# 07_LMS7002M_Power.net
KiCad netlist of a schematic drawn in Altium Designer
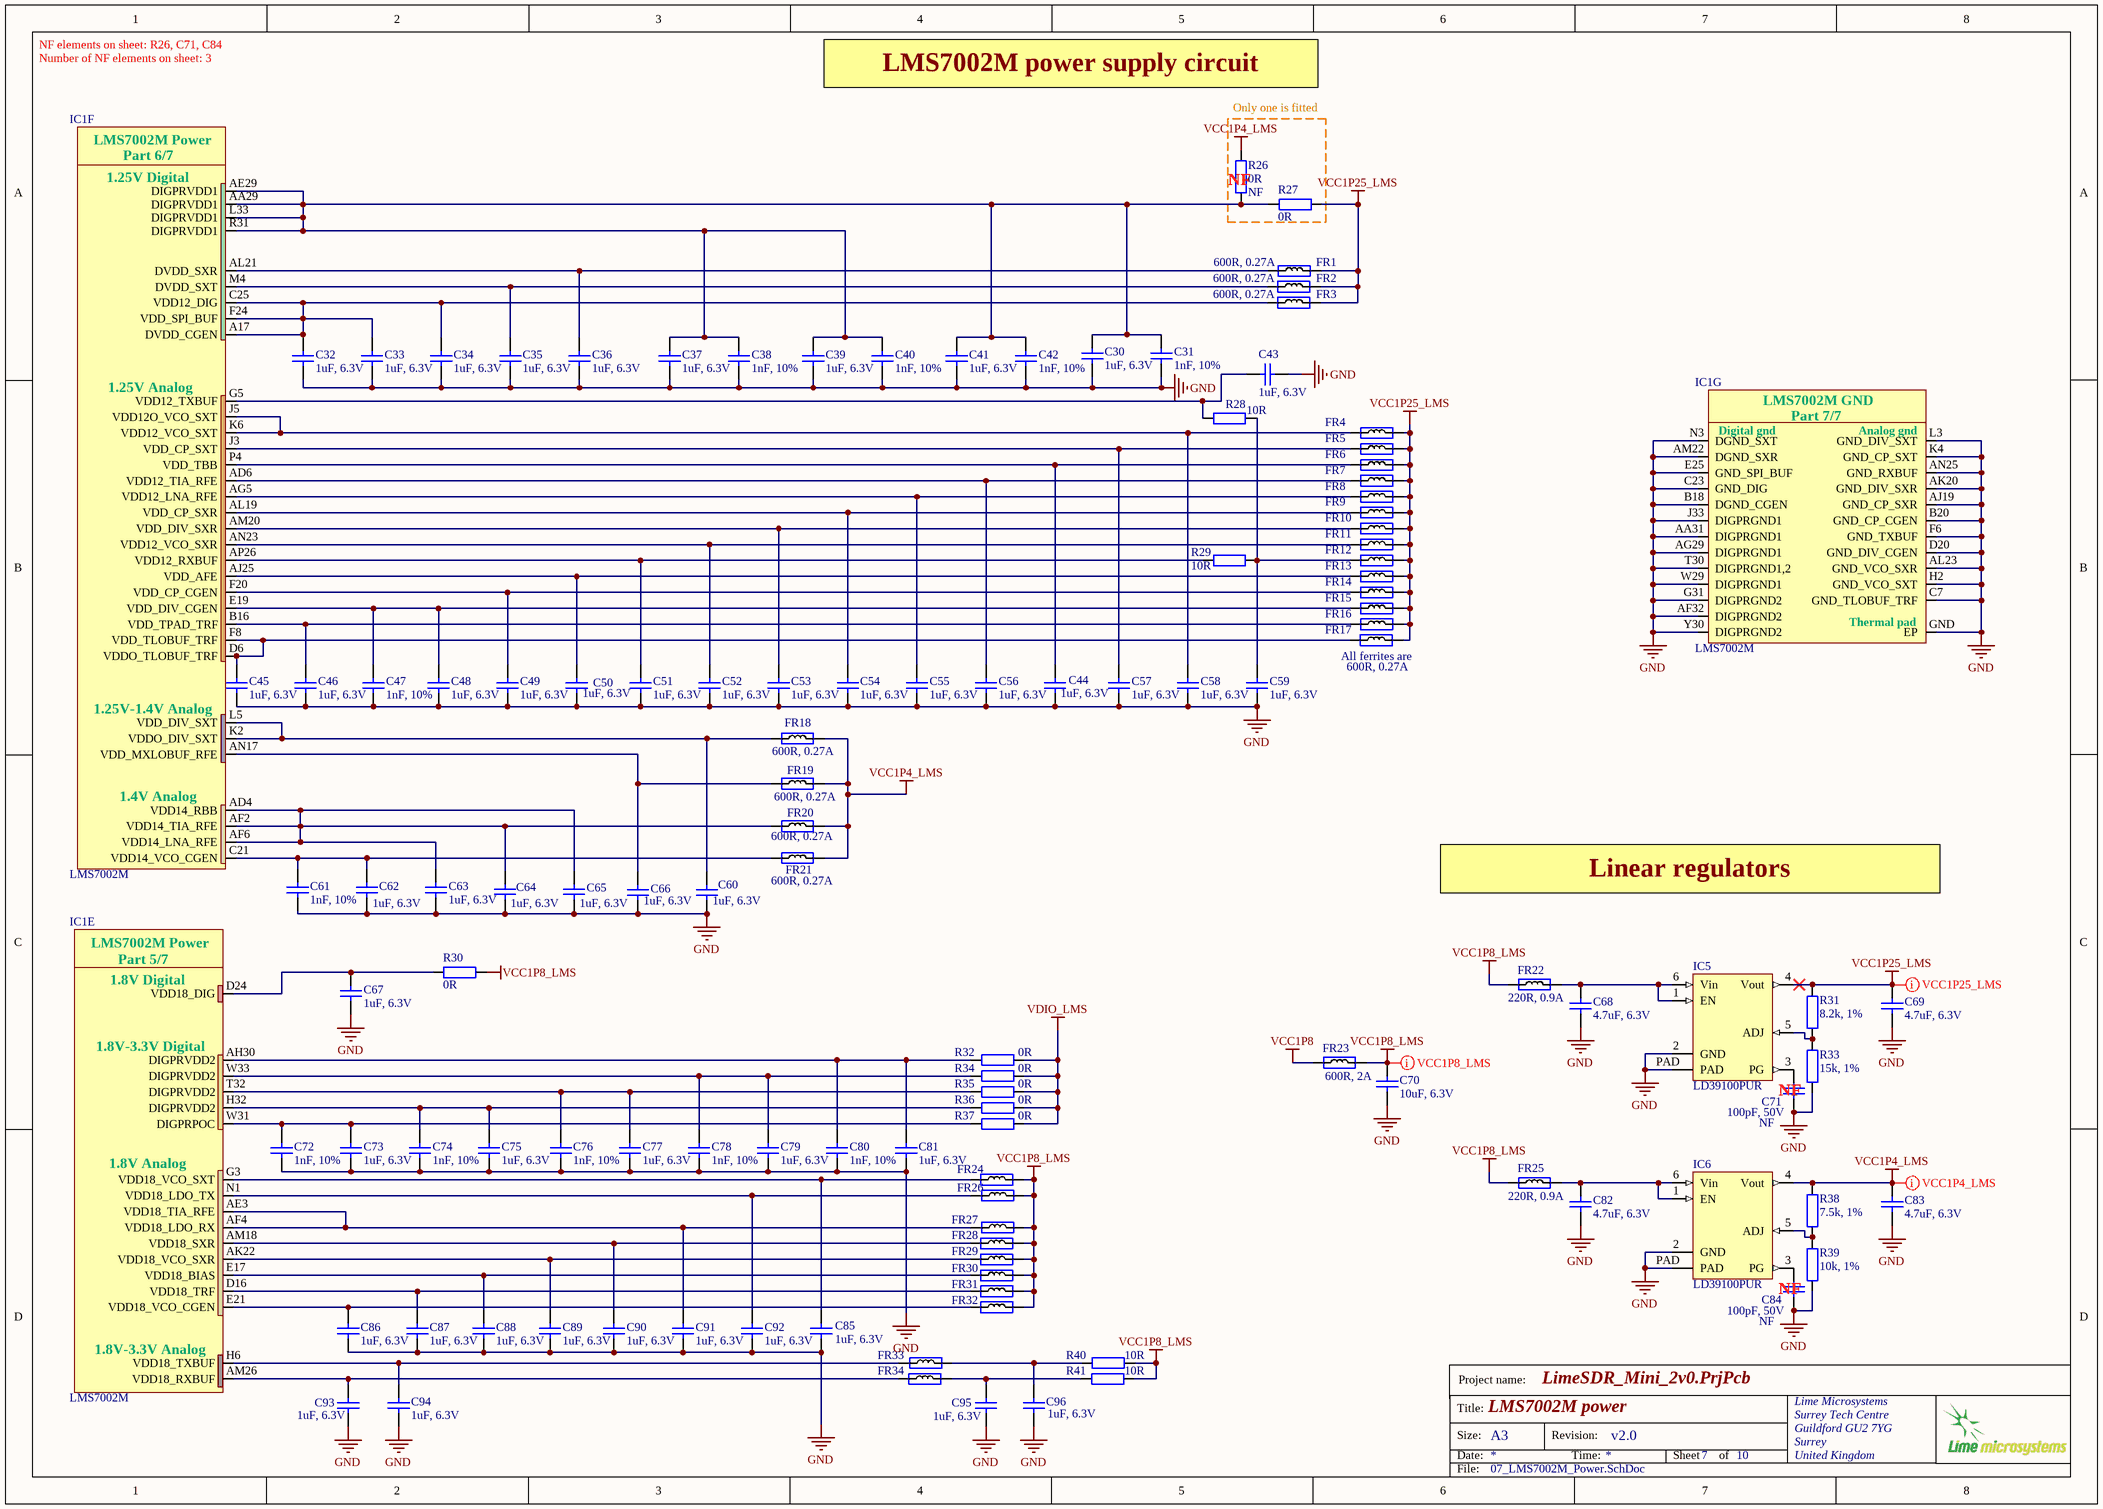
[diagram p0: 07_LMS7002M_Power.SchDoc]

(export (version "E")
  (design (tool "Eeschema 10.0.6"))
  (components
    (comp (ref "C30")
      (value "1uF, 6.3V")
      (footprint "CAP0201")
      (fields (field (name "TOLERANCE") "±20%") (field (name "MANUFACTURER") "TDK Corporation"))
      (libsource (lib "LimeMicroAltiumLib_schLib") (part "Cap_0402"))
    )
    (comp (ref "C31")
      (value "1nF, 10%")
      (footprint "CAP0201")
      (fields (field (name "TOLERANCE") "±10%") (field (name "MANUFACTURER") "TDK Corporation"))
      (libsource (lib "LimeMicroAltiumLib_schLib") (part "Cap_0402"))
    )
    (comp (ref "C32")
      (value "1uF, 6.3V")
      (footprint "CAP0201")
      (fields (field (name "TOLERANCE") "±20%") (field (name "MANUFACTURER") "TDK Corporation"))
      (libsource (lib "LimeMicroAltiumLib_schLib") (part "Cap_0402"))
    )
    (comp (ref "C33")
      (value "1uF, 6.3V")
      (footprint "CAP0201")
      (fields (field (name "TOLERANCE") "±20%") (field (name "MANUFACTURER") "TDK Corporation"))
      (libsource (lib "LimeMicroAltiumLib_schLib") (part "Cap_0402"))
    )
    (comp (ref "C34")
      (value "1uF, 6.3V")
      (footprint "CAP0201")
      (fields (field (name "TOLERANCE") "±20%") (field (name "MANUFACTURER") "TDK Corporation"))
      (libsource (lib "LimeMicroAltiumLib_schLib") (part "Cap_0402"))
    )
    (comp (ref "C35")
      (value "1uF, 6.3V")
      (footprint "CAP0201")
      (fields (field (name "TOLERANCE") "±20%") (field (name "MANUFACTURER") "TDK Corporation"))
      (libsource (lib "LimeMicroAltiumLib_schLib") (part "Cap_0402"))
    )
    (comp (ref "C36")
      (value "1uF, 6.3V")
      (footprint "CAP0201")
      (fields (field (name "TOLERANCE") "±20%") (field (name "MANUFACTURER") "TDK Corporation"))
      (libsource (lib "LimeMicroAltiumLib_schLib") (part "Cap_0402"))
    )
    (comp (ref "C37")
      (value "1uF, 6.3V")
      (footprint "CAP0201")
      (fields (field (name "TOLERANCE") "±20%") (field (name "MANUFACTURER") "TDK Corporation"))
      (libsource (lib "LimeMicroAltiumLib_schLib") (part "Cap_0402"))
    )
    (comp (ref "C38")
      (value "1nF, 10%")
      (footprint "CAP0201")
      (fields (field (name "TOLERANCE") "±10%") (field (name "MANUFACTURER") "TDK Corporation"))
      (libsource (lib "LimeMicroAltiumLib_schLib") (part "Cap_0402"))
    )
    (comp (ref "C39")
      (value "1uF, 6.3V")
      (footprint "CAP0201")
      (fields (field (name "TOLERANCE") "±20%") (field (name "MANUFACTURER") "TDK Corporation"))
      (libsource (lib "LimeMicroAltiumLib_schLib") (part "Cap_0402"))
    )
    (comp (ref "C40")
      (value "1nF, 10%")
      (footprint "CAP0201")
      (fields (field (name "TOLERANCE") "±10%") (field (name "MANUFACTURER") "TDK Corporation"))
      (libsource (lib "LimeMicroAltiumLib_schLib") (part "Cap_0402"))
    )
    (comp (ref "C41")
      (value "1uF, 6.3V")
      (footprint "CAP0201")
      (fields (field (name "TOLERANCE") "±20%") (field (name "MANUFACTURER") "TDK Corporation"))
      (libsource (lib "LimeMicroAltiumLib_schLib") (part "Cap_0402"))
    )
    (comp (ref "C42")
      (value "1nF, 10%")
      (footprint "CAP0201")
      (fields (field (name "TOLERANCE") "±10%") (field (name "MANUFACTURER") "TDK Corporation"))
      (libsource (lib "LimeMicroAltiumLib_schLib") (part "Cap_0402"))
    )
    (comp (ref "C43")
      (value "1uF, 6.3V")
      (footprint "CAP0201")
      (fields (field (name "TOLERANCE") "±20%") (field (name "MANUFACTURER") "TDK Corporation"))
      (libsource (lib "LimeMicroAltiumLib_schLib") (part "Cap_0402"))
    )
    (comp (ref "C44")
      (value "1uF, 6.3V")
      (footprint "CAP0201")
      (fields (field (name "TOLERANCE") "±20%") (field (name "MANUFACTURER") "TDK Corporation"))
      (libsource (lib "LimeMicroAltiumLib_schLib") (part "Cap_0402"))
    )
    (comp (ref "C45")
      (value "1uF, 6.3V")
      (footprint "CAP0201")
      (fields (field (name "TOLERANCE") "±20%") (field (name "MANUFACTURER") "TDK Corporation"))
      (libsource (lib "LimeMicroAltiumLib_schLib") (part "Cap_0402"))
    )
    (comp (ref "C46")
      (value "1uF, 6.3V")
      (footprint "CAP0201")
      (fields (field (name "TOLERANCE") "±20%") (field (name "MANUFACTURER") "TDK Corporation"))
      (libsource (lib "LimeMicroAltiumLib_schLib") (part "Cap_0402"))
    )
    (comp (ref "C47")
      (value "1nF, 10%")
      (footprint "CAP0201")
      (fields (field (name "TOLERANCE") "±10%") (field (name "MANUFACTURER") "TDK Corporation"))
      (libsource (lib "LimeMicroAltiumLib_schLib") (part "Cap_0402"))
    )
    (comp (ref "C48")
      (value "1uF, 6.3V")
      (footprint "CAP0201")
      (fields (field (name "TOLERANCE") "±20%") (field (name "MANUFACTURER") "TDK Corporation"))
      (libsource (lib "LimeMicroAltiumLib_schLib") (part "Cap_0402"))
    )
    (comp (ref "C49")
      (value "1uF, 6.3V")
      (footprint "CAP0201")
      (fields (field (name "TOLERANCE") "±20%") (field (name "MANUFACTURER") "TDK Corporation"))
      (libsource (lib "LimeMicroAltiumLib_schLib") (part "Cap_0402"))
    )
    (comp (ref "C50")
      (value "1uF, 6.3V")
      (footprint "CAP0201")
      (fields (field (name "TOLERANCE") "±20%") (field (name "MANUFACTURER") "TDK Corporation"))
      (libsource (lib "LimeMicroAltiumLib_schLib") (part "Cap_0402"))
    )
    (comp (ref "C51")
      (value "1uF, 6.3V")
      (footprint "CAP0201")
      (fields (field (name "TOLERANCE") "±20%") (field (name "MANUFACTURER") "TDK Corporation"))
      (libsource (lib "LimeMicroAltiumLib_schLib") (part "Cap_0402"))
    )
    (comp (ref "C52")
      (value "1uF, 6.3V")
      (footprint "CAP0201")
      (fields (field (name "TOLERANCE") "±20%") (field (name "MANUFACTURER") "TDK Corporation"))
      (libsource (lib "LimeMicroAltiumLib_schLib") (part "Cap_0402"))
    )
    (comp (ref "C53")
      (value "1uF, 6.3V")
      (footprint "CAP0201")
      (fields (field (name "TOLERANCE") "±20%") (field (name "MANUFACTURER") "TDK Corporation"))
      (libsource (lib "LimeMicroAltiumLib_schLib") (part "Cap_0402"))
    )
    (comp (ref "C54")
      (value "1uF, 6.3V")
      (footprint "CAP0201")
      (fields (field (name "TOLERANCE") "±20%") (field (name "MANUFACTURER") "TDK Corporation"))
      (libsource (lib "LimeMicroAltiumLib_schLib") (part "Cap_0402"))
    )
    (comp (ref "C55")
      (value "1uF, 6.3V")
      (footprint "CAP0201")
      (fields (field (name "TOLERANCE") "±20%") (field (name "MANUFACTURER") "TDK Corporation"))
      (libsource (lib "LimeMicroAltiumLib_schLib") (part "Cap_0402"))
    )
    (comp (ref "C56")
      (value "1uF, 6.3V")
      (footprint "CAP0201")
      (fields (field (name "TOLERANCE") "±20%") (field (name "MANUFACTURER") "TDK Corporation"))
      (libsource (lib "LimeMicroAltiumLib_schLib") (part "Cap_0402"))
    )
    (comp (ref "C57")
      (value "1uF, 6.3V")
      (footprint "CAP0201")
      (fields (field (name "TOLERANCE") "±20%") (field (name "MANUFACTURER") "TDK Corporation"))
      (libsource (lib "LimeMicroAltiumLib_schLib") (part "Cap_0402"))
    )
    (comp (ref "C58")
      (value "1uF, 6.3V")
      (footprint "CAP0201")
      (fields (field (name "TOLERANCE") "±20%") (field (name "MANUFACTURER") "TDK Corporation"))
      (libsource (lib "LimeMicroAltiumLib_schLib") (part "Cap_0402"))
    )
    (comp (ref "C59")
      (value "1uF, 6.3V")
      (footprint "CAP0201")
      (fields (field (name "TOLERANCE") "±20%") (field (name "MANUFACTURER") "TDK Corporation"))
      (libsource (lib "LimeMicroAltiumLib_schLib") (part "Cap_0402"))
    )
    (comp (ref "C60")
      (value "1uF, 6.3V")
      (footprint "CAP0201")
      (fields (field (name "TOLERANCE") "±20%") (field (name "MANUFACTURER") "TDK Corporation"))
      (libsource (lib "LimeMicroAltiumLib_schLib") (part "Cap_0402"))
    )
    (comp (ref "C61")
      (value "1nF, 10%")
      (footprint "CAP0201")
      (fields (field (name "TOLERANCE") "±10%") (field (name "MANUFACTURER") "TDK Corporation"))
      (libsource (lib "LimeMicroAltiumLib_schLib") (part "Cap_0402"))
    )
    (comp (ref "C62")
      (value "1uF, 6.3V")
      (footprint "CAP0201")
      (fields (field (name "TOLERANCE") "±20%") (field (name "MANUFACTURER") "TDK Corporation"))
      (libsource (lib "LimeMicroAltiumLib_schLib") (part "Cap_0402"))
    )
    (comp (ref "C63")
      (value "1uF, 6.3V")
      (footprint "CAP0201")
      (fields (field (name "TOLERANCE") "±20%") (field (name "MANUFACTURER") "TDK Corporation"))
      (libsource (lib "LimeMicroAltiumLib_schLib") (part "Cap_0402"))
    )
    (comp (ref "C64")
      (value "1uF, 6.3V")
      (footprint "CAP0201")
      (fields (field (name "TOLERANCE") "±20%") (field (name "MANUFACTURER") "TDK Corporation"))
      (libsource (lib "LimeMicroAltiumLib_schLib") (part "Cap_0402"))
    )
    (comp (ref "C65")
      (value "1uF, 6.3V")
      (footprint "CAP0201")
      (fields (field (name "TOLERANCE") "±20%") (field (name "MANUFACTURER") "TDK Corporation"))
      (libsource (lib "LimeMicroAltiumLib_schLib") (part "Cap_0402"))
    )
    (comp (ref "C66")
      (value "1uF, 6.3V")
      (footprint "CAP0201")
      (fields (field (name "TOLERANCE") "±20%") (field (name "MANUFACTURER") "TDK Corporation"))
      (libsource (lib "LimeMicroAltiumLib_schLib") (part "Cap_0402"))
    )
    (comp (ref "C67")
      (value "1uF, 6.3V")
      (footprint "CAP0201")
      (fields (field (name "TOLERANCE") "±20%") (field (name "MANUFACTURER") "TDK Corporation"))
      (libsource (lib "LimeMicroAltiumLib_schLib") (part "Cap_0402"))
    )
    (comp (ref "C68")
      (value "4.7uF, 6.3V")
      (footprint "CAP0402")
      (fields
        (field (name "MANUFACTURER") "Murata Electronics North America")
        (field (name "TOLERANCE") "±20%")
      )
      (libsource (lib "LimeMicroAltiumLib_schLib") (part "Cap_0402"))
    )
    (comp (ref "C69")
      (value "4.7uF, 6.3V")
      (footprint "CAP0402")
      (fields
        (field (name "MANUFACTURER") "Murata Electronics North America")
        (field (name "TOLERANCE") "±20%")
      )
      (libsource (lib "LimeMicroAltiumLib_schLib") (part "Cap_0402"))
    )
    (comp (ref "C70")
      (value "10uF, 6.3V")
      (footprint "CAP0603")
      (fields (field (name "TOLERANCE") "±20%") (field (name "MANUFACTURER") "Yageo"))
      (libsource (lib "LimeFPGAboard_schLib") (part "Cap_0603"))
    )
    (comp (ref "C71")
      (value "100pF, 50V")
      (footprint "CAP0402")
      (fields
        (field (name "ASSEMBLY INFO") "NF")
        (field (name "MANUFACTURER") "Yageo")
        (field (name "TOLERANCE") "±5%")
      )
      (libsource (lib "LimeMicroAltiumLib_schLib") (part "Cap_0402"))
    )
    (comp (ref "C72")
      (value "1nF, 10%")
      (footprint "CAP0201")
      (fields (field (name "TOLERANCE") "±10%") (field (name "MANUFACTURER") "TDK Corporation"))
      (libsource (lib "LimeMicroAltiumLib_schLib") (part "Cap_0402"))
    )
    (comp (ref "C73")
      (value "1uF, 6.3V")
      (footprint "CAP0201")
      (fields (field (name "TOLERANCE") "±20%") (field (name "MANUFACTURER") "TDK Corporation"))
      (libsource (lib "LimeMicroAltiumLib_schLib") (part "Cap_0402"))
    )
    (comp (ref "C74")
      (value "1nF, 10%")
      (footprint "CAP0201")
      (fields (field (name "TOLERANCE") "±10%") (field (name "MANUFACTURER") "TDK Corporation"))
      (libsource (lib "LimeMicroAltiumLib_schLib") (part "Cap_0402"))
    )
    (comp (ref "C75")
      (value "1uF, 6.3V")
      (footprint "CAP0201")
      (fields (field (name "TOLERANCE") "±20%") (field (name "MANUFACTURER") "TDK Corporation"))
      (libsource (lib "LimeMicroAltiumLib_schLib") (part "Cap_0402"))
    )
    (comp (ref "C76")
      (value "1nF, 10%")
      (footprint "CAP0201")
      (fields (field (name "TOLERANCE") "±10%") (field (name "MANUFACTURER") "TDK Corporation"))
      (libsource (lib "LimeMicroAltiumLib_schLib") (part "Cap_0402"))
    )
    (comp (ref "C77")
      (value "1uF, 6.3V")
      (footprint "CAP0201")
      (fields (field (name "TOLERANCE") "±20%") (field (name "MANUFACTURER") "TDK Corporation"))
      (libsource (lib "LimeMicroAltiumLib_schLib") (part "Cap_0402"))
    )
    (comp (ref "C78")
      (value "1nF, 10%")
      (footprint "CAP0201")
      (fields (field (name "TOLERANCE") "±10%") (field (name "MANUFACTURER") "TDK Corporation"))
      (libsource (lib "LimeMicroAltiumLib_schLib") (part "Cap_0402"))
    )
    (comp (ref "C79")
      (value "1uF, 6.3V")
      (footprint "CAP0201")
      (fields (field (name "TOLERANCE") "±20%") (field (name "MANUFACTURER") "TDK Corporation"))
      (libsource (lib "LimeMicroAltiumLib_schLib") (part "Cap_0402"))
    )
    (comp (ref "C80")
      (value "1nF, 10%")
      (footprint "CAP0201")
      (fields (field (name "TOLERANCE") "±10%") (field (name "MANUFACTURER") "TDK Corporation"))
      (libsource (lib "LimeMicroAltiumLib_schLib") (part "Cap_0402"))
    )
    (comp (ref "C81")
      (value "1uF, 6.3V")
      (footprint "CAP0201")
      (fields (field (name "TOLERANCE") "±20%") (field (name "MANUFACTURER") "TDK Corporation"))
      (libsource (lib "LimeMicroAltiumLib_schLib") (part "Cap_0402"))
    )
    (comp (ref "C82")
      (value "4.7uF, 6.3V")
      (footprint "CAP0402")
      (fields
        (field (name "MANUFACTURER") "Murata Electronics North America")
        (field (name "TOLERANCE") "±20%")
      )
      (libsource (lib "LimeMicroAltiumLib_schLib") (part "Cap_0402"))
    )
    (comp (ref "C83")
      (value "4.7uF, 6.3V")
      (footprint "CAP0402")
      (fields
        (field (name "MANUFACTURER") "Murata Electronics North America")
        (field (name "TOLERANCE") "±20%")
      )
      (libsource (lib "LimeMicroAltiumLib_schLib") (part "Cap_0402"))
    )
    (comp (ref "C84")
      (value "100pF, 50V")
      (footprint "CAP0402")
      (fields
        (field (name "ASSEMBLY INFO") "NF")
        (field (name "MANUFACTURER") "Yageo")
        (field (name "TOLERANCE") "±5%")
      )
      (libsource (lib "LimeMicroAltiumLib_schLib") (part "Cap_0402"))
    )
    (comp (ref "C85")
      (value "1uF, 6.3V")
      (footprint "CAP0201")
      (fields (field (name "TOLERANCE") "±20%") (field (name "MANUFACTURER") "TDK Corporation"))
      (libsource (lib "LimeMicroAltiumLib_schLib") (part "Cap_0402"))
    )
    (comp (ref "C86")
      (value "1uF, 6.3V")
      (footprint "CAP0201")
      (fields (field (name "TOLERANCE") "±20%") (field (name "MANUFACTURER") "TDK Corporation"))
      (libsource (lib "LimeMicroAltiumLib_schLib") (part "Cap_0402"))
    )
    (comp (ref "C87")
      (value "1uF, 6.3V")
      (footprint "CAP0201")
      (fields (field (name "TOLERANCE") "±20%") (field (name "MANUFACTURER") "TDK Corporation"))
      (libsource (lib "LimeMicroAltiumLib_schLib") (part "Cap_0402"))
    )
    (comp (ref "C88")
      (value "1uF, 6.3V")
      (footprint "CAP0201")
      (fields (field (name "TOLERANCE") "±20%") (field (name "MANUFACTURER") "TDK Corporation"))
      (libsource (lib "LimeMicroAltiumLib_schLib") (part "Cap_0402"))
    )
    (comp (ref "C89")
      (value "1uF, 6.3V")
      (footprint "CAP0201")
      (fields (field (name "TOLERANCE") "±20%") (field (name "MANUFACTURER") "TDK Corporation"))
      (libsource (lib "LimeMicroAltiumLib_schLib") (part "Cap_0402"))
    )
    (comp (ref "C90")
      (value "1uF, 6.3V")
      (footprint "CAP0201")
      (fields (field (name "TOLERANCE") "±20%") (field (name "MANUFACTURER") "TDK Corporation"))
      (libsource (lib "LimeMicroAltiumLib_schLib") (part "Cap_0402"))
    )
    (comp (ref "C91")
      (value "1uF, 6.3V")
      (footprint "CAP0201")
      (fields (field (name "TOLERANCE") "±20%") (field (name "MANUFACTURER") "TDK Corporation"))
      (libsource (lib "LimeMicroAltiumLib_schLib") (part "Cap_0402"))
    )
    (comp (ref "C92")
      (value "1uF, 6.3V")
      (footprint "CAP0201")
      (fields (field (name "TOLERANCE") "±20%") (field (name "MANUFACTURER") "TDK Corporation"))
      (libsource (lib "LimeMicroAltiumLib_schLib") (part "Cap_0402"))
    )
    (comp (ref "C93")
      (value "1uF, 6.3V")
      (footprint "CAP0201")
      (fields (field (name "TOLERANCE") "±20%") (field (name "MANUFACTURER") "TDK Corporation"))
      (libsource (lib "LimeMicroAltiumLib_schLib") (part "Cap_0402"))
    )
    (comp (ref "C94")
      (value "1uF, 6.3V")
      (footprint "CAP0201")
      (fields (field (name "TOLERANCE") "±20%") (field (name "MANUFACTURER") "TDK Corporation"))
      (libsource (lib "LimeMicroAltiumLib_schLib") (part "Cap_0402"))
    )
    (comp (ref "C95")
      (value "1uF, 6.3V")
      (footprint "CAP0201")
      (fields (field (name "TOLERANCE") "±20%") (field (name "MANUFACTURER") "TDK Corporation"))
      (libsource (lib "LimeMicroAltiumLib_schLib") (part "Cap_0402"))
    )
    (comp (ref "C96")
      (value "1uF, 6.3V")
      (footprint "CAP0201")
      (fields (field (name "TOLERANCE") "±20%") (field (name "MANUFACTURER") "TDK Corporation"))
      (libsource (lib "LimeMicroAltiumLib_schLib") (part "Cap_0402"))
    )
    (comp (ref "FR1")
      (value "600R, 0.27A")
      (footprint "RES0201")
      (fields (field (name "MANUFACTURER") "Taiyo Yuden"))
      (libsource (lib "LimeMicroAltiumLib_schLib") (part "Ferrite"))
    )
    (comp (ref "FR2")
      (value "600R, 0.27A")
      (footprint "RES0201")
      (fields (field (name "MANUFACTURER") "Taiyo Yuden"))
      (libsource (lib "LimeMicroAltiumLib_schLib") (part "Ferrite"))
    )
    (comp (ref "FR3")
      (value "600R, 0.27A")
      (footprint "RES0201")
      (fields (field (name "MANUFACTURER") "Taiyo Yuden"))
      (libsource (lib "LimeMicroAltiumLib_schLib") (part "Ferrite"))
    )
    (comp (ref "FR4")
      (value "600R, 0.27A")
      (footprint "RES0201")
      (fields (field (name "MANUFACTURER") "Taiyo Yuden"))
      (libsource (lib "LimeMicroAltiumLib_schLib") (part "Ferrite"))
    )
    (comp (ref "FR5")
      (value "600R, 0.27A")
      (footprint "RES0201")
      (fields (field (name "MANUFACTURER") "Taiyo Yuden"))
      (libsource (lib "LimeMicroAltiumLib_schLib") (part "Ferrite"))
    )
    (comp (ref "FR6")
      (value "600R, 0.27A")
      (footprint "RES0201")
      (fields (field (name "MANUFACTURER") "Taiyo Yuden"))
      (libsource (lib "LimeMicroAltiumLib_schLib") (part "Ferrite"))
    )
    (comp (ref "FR7")
      (value "600R, 0.27A")
      (footprint "RES0201")
      (fields (field (name "MANUFACTURER") "Taiyo Yuden"))
      (libsource (lib "LimeMicroAltiumLib_schLib") (part "Ferrite"))
    )
    (comp (ref "FR8")
      (value "600R, 0.27A")
      (footprint "RES0201")
      (fields (field (name "MANUFACTURER") "Taiyo Yuden"))
      (libsource (lib "LimeMicroAltiumLib_schLib") (part "Ferrite"))
    )
    (comp (ref "FR9")
      (value "600R, 0.27A")
      (footprint "RES0201")
      (fields (field (name "MANUFACTURER") "Taiyo Yuden"))
      (libsource (lib "LimeMicroAltiumLib_schLib") (part "Ferrite"))
    )
    (comp (ref "FR10")
      (value "600R, 0.27A")
      (footprint "RES0201")
      (fields (field (name "MANUFACTURER") "Taiyo Yuden"))
      (libsource (lib "LimeMicroAltiumLib_schLib") (part "Ferrite"))
    )
    (comp (ref "FR11")
      (value "600R, 0.27A")
      (footprint "RES0201")
      (fields (field (name "MANUFACTURER") "Taiyo Yuden"))
      (libsource (lib "LimeMicroAltiumLib_schLib") (part "Ferrite"))
    )
    (comp (ref "FR12")
      (value "600R, 0.27A")
      (footprint "RES0201")
      (fields (field (name "MANUFACTURER") "Taiyo Yuden"))
      (libsource (lib "LimeMicroAltiumLib_schLib") (part "Ferrite"))
    )
    (comp (ref "FR13")
      (value "600R, 0.27A")
      (footprint "RES0201")
      (fields (field (name "MANUFACTURER") "Taiyo Yuden"))
      (libsource (lib "LimeMicroAltiumLib_schLib") (part "Ferrite"))
    )
    (comp (ref "FR14")
      (value "600R, 0.27A")
      (footprint "RES0201")
      (fields (field (name "MANUFACTURER") "Taiyo Yuden"))
      (libsource (lib "LimeMicroAltiumLib_schLib") (part "Ferrite"))
    )
    (comp (ref "FR15")
      (value "600R, 0.27A")
      (footprint "RES0201")
      (fields (field (name "MANUFACTURER") "Taiyo Yuden"))
      (libsource (lib "LimeMicroAltiumLib_schLib") (part "Ferrite"))
    )
    (comp (ref "FR16")
      (value "600R, 0.27A")
      (footprint "RES0201")
      (fields (field (name "MANUFACTURER") "Taiyo Yuden"))
      (libsource (lib "LimeMicroAltiumLib_schLib") (part "Ferrite"))
    )
    (comp (ref "FR17")
      (value "600R, 0.27A")
      (footprint "RES0201")
      (fields (field (name "MANUFACTURER") "Taiyo Yuden"))
      (libsource (lib "LimeMicroAltiumLib_schLib") (part "Ferrite"))
    )
    (comp (ref "FR18")
      (value "600R, 0.27A")
      (footprint "RES0201")
      (fields (field (name "MANUFACTURER") "Taiyo Yuden"))
      (libsource (lib "LimeMicroAltiumLib_schLib") (part "Ferrite"))
    )
    (comp (ref "FR19")
      (value "600R, 0.27A")
      (footprint "RES0201")
      (fields (field (name "MANUFACTURER") "Taiyo Yuden"))
      (libsource (lib "LimeMicroAltiumLib_schLib") (part "Ferrite"))
    )
    (comp (ref "FR20")
      (value "600R, 0.27A")
      (footprint "RES0201")
      (fields (field (name "MANUFACTURER") "Taiyo Yuden"))
      (libsource (lib "LimeMicroAltiumLib_schLib") (part "Ferrite"))
    )
    (comp (ref "FR21")
      (value "600R, 0.27A")
      (footprint "RES0201")
      (fields (field (name "MANUFACTURER") "Taiyo Yuden"))
      (libsource (lib "LimeMicroAltiumLib_schLib") (part "Ferrite"))
    )
    (comp (ref "FR22")
      (value "220R, 0.9A")
      (footprint "RES0402")
      (fields (field (name "MANUFACTURER") "TDK Corporation"))
      (libsource (lib "LimeFPGAboard_schLib") (part "Ferrite"))
    )
    (comp (ref "FR23")
      (value "600R, 2A")
      (footprint "RES0805")
      (fields (field (name "MANUFACTURER") "TDK Corporation"))
      (libsource (lib "LimeMicroAltiumLib_schLib") (part "Ferrite"))
    )
    (comp (ref "FR24")
      (value "600R, 0.27A")
      (footprint "RES0201")
      (fields (field (name "MANUFACTURER") "Taiyo Yuden"))
      (libsource (lib "LimeMicroAltiumLib_schLib") (part "Ferrite"))
    )
    (comp (ref "FR25")
      (value "220R, 0.9A")
      (footprint "RES0402")
      (fields (field (name "MANUFACTURER") "TDK Corporation"))
      (libsource (lib "LimeFPGAboard_schLib") (part "Ferrite"))
    )
    (comp (ref "FR26")
      (value "600R, 0.27A")
      (footprint "RES0201")
      (fields (field (name "MANUFACTURER") "Taiyo Yuden"))
      (libsource (lib "") (part "Ferrite_1"))
    )
    (comp (ref "FR27")
      (value "600R, 0.27A")
      (footprint "RES0201")
      (fields (field (name "MANUFACTURER") "Taiyo Yuden"))
      (libsource (lib "") (part "Ferrite_1"))
    )
    (comp (ref "FR28")
      (value "600R, 0.27A")
      (footprint "RES0201")
      (fields (field (name "MANUFACTURER") "Taiyo Yuden"))
      (libsource (lib "LimeMicroAltiumLib_schLib") (part "Ferrite"))
    )
    (comp (ref "FR29")
      (value "600R, 0.27A")
      (footprint "RES0201")
      (fields (field (name "MANUFACTURER") "Taiyo Yuden"))
      (libsource (lib "LimeMicroAltiumLib_schLib") (part "Ferrite"))
    )
    (comp (ref "FR30")
      (value "600R, 0.27A")
      (footprint "RES0201")
      (fields (field (name "MANUFACTURER") "Taiyo Yuden"))
      (libsource (lib "LimeMicroAltiumLib_schLib") (part "Ferrite"))
    )
    (comp (ref "FR31")
      (value "600R, 0.27A")
      (footprint "RES0201")
      (fields (field (name "MANUFACTURER") "Taiyo Yuden"))
      (libsource (lib "LimeMicroAltiumLib_schLib") (part "Ferrite"))
    )
    (comp (ref "FR32")
      (value "600R, 0.27A")
      (footprint "RES0201")
      (fields (field (name "MANUFACTURER") "Taiyo Yuden"))
      (libsource (lib "LimeMicroAltiumLib_schLib") (part "Ferrite"))
    )
    (comp (ref "FR33")
      (value "600R, 0.27A")
      (footprint "RES0201")
      (fields (field (name "MANUFACTURER") "Taiyo Yuden"))
      (libsource (lib "") (part "Ferrite_1"))
    )
    (comp (ref "FR34")
      (value "600R, 0.27A")
      (footprint "RES0201")
      (fields (field (name "MANUFACTURER") "Taiyo Yuden"))
      (libsource (lib "LimeMicroAltiumLib_schLib") (part "Ferrite"))
    )
    (comp (ref "IC1")
      (value "LMS7002M")
      (footprint "LMS7002M_v5")
      (description "Schematic symbol revision 3. Default footprint - 0.31mm pad")
      (fields (field (name "MANUFACTURER") "Lime Microsystems"))
      (libsource (lib "LimeMicroAltiumLib_schLib") (part "LMS7002Mr3"))
    )
    (comp (ref "IC5")
      (value "LD39100PUR")
      (footprint "LD39100PUR")
      (fields (field (name "MANUFACTURER") "STMicroelectronics"))
      (libsource (lib "LimeMicroAltiumLib_schLib") (part "LD39100PUR"))
    )
    (comp (ref "IC6")
      (value "LD39100PUR")
      (footprint "LD39100PUR")
      (fields (field (name "MANUFACTURER") "STMicroelectronics"))
      (libsource (lib "LimeMicroAltiumLib_schLib") (part "LD39100PUR"))
    )
    (comp (ref "R26")
      (value "0R")
      (footprint "RES0402")
      (fields
        (field (name "ASSEMBLY INFO") "NF")
        (field (name "MANUFACTURER") "Yageo")
        (field (name "TOLERANCE") "Jumper")
      )
      (libsource (lib "LimeMicroAltiumLib_schLib") (part "Res_0402"))
    )
    (comp (ref "R27")
      (value "0R")
      (footprint "RES0402")
      (fields (field (name "MANUFACTURER") "Yageo") (field (name "TOLERANCE") "Jumper"))
      (libsource (lib "LimeMicroAltiumLib_schLib") (part "Res_0402"))
    )
    (comp (ref "R28")
      (value "10R")
      (footprint "RES0201")
      (fields
        (field (name "MANUFACTURER") "Panasonic Electronic Components")
        (field (name "TOLERANCE") "±1%")
      )
      (libsource (lib "LimeMicroAltiumLib_schLib") (part "Res_0402"))
    )
    (comp (ref "R29")
      (value "10R")
      (footprint "RES0201")
      (fields
        (field (name "MANUFACTURER") "Panasonic Electronic Components")
        (field (name "TOLERANCE") "±1%")
      )
      (libsource (lib "LimeMicroAltiumLib_schLib") (part "Res_0402"))
    )
    (comp (ref "R30")
      (value "0R")
      (footprint "RES0201")
      (fields (field (name "MANUFACTURER") "Rohm Semiconductor") (field (name "TOLERANCE") "Jumper"))
      (libsource (lib "LimeMicroAltiumLib_schLib") (part "Res_0402"))
    )
    (comp (ref "R31")
      (value "8.2k, 1%")
      (footprint "RES0402")
      (fields (field (name "MANUFACTURER") "Yageo") (field (name "TOLERANCE") "±1%"))
      (libsource (lib "LimeMicroAltiumLib_schLib") (part "Res_0402"))
    )
    (comp (ref "R32")
      (value "0R")
      (footprint "RES0402")
      (fields (field (name "MANUFACTURER") "Yageo") (field (name "TOLERANCE") "Jumper"))
      (libsource (lib "LimeMicroAltiumLib_schLib") (part "Res_0402"))
    )
    (comp (ref "R33")
      (value "15k, 1%")
      (footprint "RES0402")
      (fields (field (name "TOLERANCE") "±1%") (field (name "MANUFACTURER") "Yageo"))
      (libsource (lib "LimeMicroAltiumLib_schLib") (part "Res_0402"))
    )
    (comp (ref "R34")
      (value "0R")
      (footprint "RES0402")
      (fields (field (name "MANUFACTURER") "Yageo") (field (name "TOLERANCE") "Jumper"))
      (libsource (lib "LimeMicroAltiumLib_schLib") (part "Res_0402"))
    )
    (comp (ref "R35")
      (value "0R")
      (footprint "RES0402")
      (fields (field (name "MANUFACTURER") "Yageo") (field (name "TOLERANCE") "Jumper"))
      (libsource (lib "LimeMicroAltiumLib_schLib") (part "Res_0402"))
    )
    (comp (ref "R36")
      (value "0R")
      (footprint "RES0402")
      (fields (field (name "MANUFACTURER") "Yageo") (field (name "TOLERANCE") "Jumper"))
      (libsource (lib "LimeMicroAltiumLib_schLib") (part "Res_0402"))
    )
    (comp (ref "R37")
      (value "0R")
      (footprint "RES0402")
      (fields (field (name "MANUFACTURER") "Yageo") (field (name "TOLERANCE") "Jumper"))
      (libsource (lib "LimeMicroAltiumLib_schLib") (part "Res_0402"))
    )
    (comp (ref "R38")
      (value "7.5k, 1%")
      (footprint "RES0402")
      (fields (field (name "MANUFACTURER") "Yageo") (field (name "TOLERANCE") "±1%"))
      (libsource (lib "LimeMicroAltiumLib_schLib") (part "Res_0402"))
    )
    (comp (ref "R39")
      (value "10k, 1%")
      (footprint "RES0402")
      (fields (field (name "MANUFACTURER") "Yageo") (field (name "TOLERANCE") "±1%"))
      (libsource (lib "LimeMicroAltiumLib_schLib") (part "Res_0402"))
    )
    (comp (ref "R40")
      (value "10R")
      (footprint "RES0201")
      (fields
        (field (name "MANUFACTURER") "Panasonic Electronic Components")
        (field (name "TOLERANCE") "±1%")
      )
      (libsource (lib "LimeMicroAltiumLib_schLib") (part "Res_0402"))
    )
    (comp (ref "R41")
      (value "10R")
      (footprint "RES0201")
      (fields
        (field (name "MANUFACTURER") "Panasonic Electronic Components")
        (field (name "TOLERANCE") "±1%")
      )
      (libsource (lib "LimeMicroAltiumLib_schLib") (part "Res_0402"))
    )
  )
  (nets
    (net (code "1") (name "GND") (class "Default")
      (node (ref "C30") (pin "2") (pinfunction "2_2") (pintype "passive"))
      (node (ref "C31") (pin "2") (pinfunction "2_2") (pintype "passive"))
      (node (ref "C32") (pin "2") (pinfunction "2_2") (pintype "passive"))
      (node (ref "C33") (pin "2") (pinfunction "2_2") (pintype "passive"))
      (node (ref "C34") (pin "2") (pinfunction "2_2") (pintype "passive"))
      (node (ref "C35") (pin "1") (pinfunction "1_1") (pintype "passive"))
      (node (ref "C36") (pin "2") (pinfunction "2_2") (pintype "passive"))
      (node (ref "C37") (pin "2") (pinfunction "2_2") (pintype "passive"))
      (node (ref "C38") (pin "2") (pinfunction "2_2") (pintype "passive"))
      (node (ref "C39") (pin "2") (pinfunction "2_2") (pintype "passive"))
      (node (ref "C40") (pin "2") (pinfunction "2_2") (pintype "passive"))
      (node (ref "C41") (pin "2") (pinfunction "2_2") (pintype "passive"))
      (node (ref "C42") (pin "2") (pinfunction "2_2") (pintype "passive"))
      (node (ref "C43") (pin "2") (pinfunction "2_2") (pintype "passive"))
      (node (ref "C44") (pin "2") (pinfunction "2_2") (pintype "passive"))
      (node (ref "C45") (pin "2") (pinfunction "2_2") (pintype "passive"))
      (node (ref "C46") (pin "2") (pinfunction "2_2") (pintype "passive"))
      (node (ref "C47") (pin "2") (pinfunction "2_2") (pintype "passive"))
      (node (ref "C48") (pin "2") (pinfunction "2_2") (pintype "passive"))
      (node (ref "C49") (pin "1") (pinfunction "1_1") (pintype "passive"))
      (node (ref "C50") (pin "2") (pinfunction "2_2") (pintype "passive"))
      (node (ref "C51") (pin "2") (pinfunction "2_2") (pintype "passive"))
      (node (ref "C52") (pin "2") (pinfunction "2_2") (pintype "passive"))
      (node (ref "C53") (pin "2") (pinfunction "2_2") (pintype "passive"))
      (node (ref "C54") (pin "2") (pinfunction "2_2") (pintype "passive"))
      (node (ref "C55") (pin "2") (pinfunction "2_2") (pintype "passive"))
      (node (ref "C56") (pin "1") (pinfunction "1_1") (pintype "passive"))
      (node (ref "C57") (pin "2") (pinfunction "2_2") (pintype "passive"))
      (node (ref "C58") (pin "1") (pinfunction "1_1") (pintype "passive"))
      (node (ref "C59") (pin "1") (pinfunction "1_1") (pintype "passive"))
      (node (ref "C60") (pin "2") (pinfunction "2_2") (pintype "passive"))
      (node (ref "C61") (pin "2") (pinfunction "2_2") (pintype "passive"))
      (node (ref "C62") (pin "2") (pinfunction "2_2") (pintype "passive"))
      (node (ref "C63") (pin "2") (pinfunction "2_2") (pintype "passive"))
      (node (ref "C64") (pin "2") (pinfunction "2_2") (pintype "passive"))
      (node (ref "C65") (pin "2") (pinfunction "2_2") (pintype "passive"))
      (node (ref "C66") (pin "2") (pinfunction "2_2") (pintype "passive"))
      (node (ref "C67") (pin "2") (pinfunction "2_2") (pintype "passive"))
      (node (ref "C68") (pin "1") (pinfunction "1_1") (pintype "passive"))
      (node (ref "C69") (pin "1") (pinfunction "1_1") (pintype "passive"))
      (node (ref "C70") (pin "1") (pinfunction "1_1") (pintype "passive"))
      (node (ref "C71") (pin "1") (pinfunction "1_1") (pintype "passive"))
      (node (ref "C72") (pin "2") (pinfunction "2_2") (pintype "passive"))
      (node (ref "C73") (pin "2") (pinfunction "2_2") (pintype "passive"))
      (node (ref "C74") (pin "2") (pinfunction "2_2") (pintype "passive"))
      (node (ref "C75") (pin "2") (pinfunction "2_2") (pintype "passive"))
      (node (ref "C76") (pin "2") (pinfunction "2_2") (pintype "passive"))
      (node (ref "C77") (pin "2") (pinfunction "2_2") (pintype "passive"))
      (node (ref "C78") (pin "2") (pinfunction "2_2") (pintype "passive"))
      (node (ref "C79") (pin "2") (pinfunction "2_2") (pintype "passive"))
      (node (ref "C80") (pin "2") (pinfunction "2_2") (pintype "passive"))
      (node (ref "C81") (pin "2") (pinfunction "2_2") (pintype "passive"))
      (node (ref "C82") (pin "1") (pinfunction "1_1") (pintype "passive"))
      (node (ref "C83") (pin "1") (pinfunction "1_1") (pintype "passive"))
      (node (ref "C84") (pin "1") (pinfunction "1_1") (pintype "passive"))
      (node (ref "C85") (pin "2") (pinfunction "2_2") (pintype "passive"))
      (node (ref "C86") (pin "2") (pinfunction "2_2") (pintype "passive"))
      (node (ref "C87") (pin "2") (pinfunction "2_2") (pintype "passive"))
      (node (ref "C88") (pin "2") (pinfunction "2_2") (pintype "passive"))
      (node (ref "C89") (pin "2") (pinfunction "2_2") (pintype "passive"))
      (node (ref "C90") (pin "2") (pinfunction "2_2") (pintype "passive"))
      (node (ref "C91") (pin "2") (pinfunction "2_2") (pintype "passive"))
      (node (ref "C92") (pin "2") (pinfunction "2_2") (pintype "passive"))
      (node (ref "C93") (pin "2") (pinfunction "2_2") (pintype "passive"))
      (node (ref "C94") (pin "2") (pinfunction "2_2") (pintype "passive"))
      (node (ref "C95") (pin "2") (pinfunction "2_2") (pintype "passive"))
      (node (ref "C96") (pin "2") (pinfunction "2_2") (pintype "passive"))
      (node (ref "IC1") (pin "AA31") (pinfunction "DIGPRGND1_AA31") (pintype "passive"))
      (node (ref "IC1") (pin "AF32") (pinfunction "DIGPRGND2_AF32") (pintype "passive"))
      (node (ref "IC1") (pin "AG29") (pinfunction "DIGPRGND1_AG29") (pintype "passive"))
      (node (ref "IC1") (pin "AJ19") (pinfunction "GND_CP_SXR_AJ19") (pintype "passive"))
      (node (ref "IC1") (pin "AK20") (pinfunction "GND_DIV_SXR_AK20") (pintype "passive"))
      (node (ref "IC1") (pin "AL23") (pinfunction "GND_VCO_SXR_AL23") (pintype "passive"))
      (node (ref "IC1") (pin "AM22") (pinfunction "DGND_SXR_AM22") (pintype "passive"))
      (node (ref "IC1") (pin "AN25") (pinfunction "GND_RXBUF_AN25") (pintype "passive"))
      (node (ref "IC1") (pin "B18") (pinfunction "DGND_CGEN_B18") (pintype "passive"))
      (node (ref "IC1") (pin "B20") (pinfunction "GND_CP_CGEN_B20") (pintype "passive"))
      (node (ref "IC1") (pin "C23") (pinfunction "GND_DIG_C23") (pintype "passive"))
      (node (ref "IC1") (pin "C7") (pinfunction "GND_TLOBUF_TRF_C7") (pintype "passive"))
      (node (ref "IC1") (pin "D20") (pinfunction "GND_DIV_CGEN_D20") (pintype "passive"))
      (node (ref "IC1") (pin "E25") (pinfunction "GND_SPI_BUF_E25") (pintype "passive"))
      (node (ref "IC1") (pin "F6") (pinfunction "GND_TXBUF_F6") (pintype "passive"))
      (node (ref "IC1") (pin "G31") (pinfunction "DIGPRGND2_G31") (pintype "passive"))
      (node (ref "IC1") (pin "GND") (pinfunction "EP_GND") (pintype "passive"))
      (node (ref "IC1") (pin "H2") (pinfunction "GND_VCO_SXT_H2") (pintype "passive"))
      (node (ref "IC1") (pin "J33") (pinfunction "DIGPRGND1_J33") (pintype "passive"))
      (node (ref "IC1") (pin "K4") (pinfunction "GND_CP_SXT_K4") (pintype "passive"))
      (node (ref "IC1") (pin "L3") (pinfunction "GND_DIV_SXT_L3") (pintype "passive"))
      (node (ref "IC1") (pin "N3") (pinfunction "DGND_SXT_N3") (pintype "passive"))
      (node (ref "IC1") (pin "T30") (pinfunction "DIGPRGND1,2_T30") (pintype "passive"))
      (node (ref "IC1") (pin "W29") (pinfunction "DIGPRGND1_W29") (pintype "passive"))
      (node (ref "IC1") (pin "Y30") (pinfunction "DIGPRGND2_Y30") (pintype "passive"))
      (node (ref "IC5") (pin "2") (pinfunction "GND_2") (pintype "passive"))
      (node (ref "IC5") (pin "PAD") (pinfunction "PAD_PAD") (pintype "passive"))
      (node (ref "IC6") (pin "2") (pinfunction "GND_2") (pintype "passive"))
      (node (ref "IC6") (pin "PAD") (pinfunction "PAD_PAD") (pintype "passive"))
      (node (ref "R33") (pin "1") (pinfunction "1_1") (pintype "passive"))
      (node (ref "R39") (pin "1") (pinfunction "1_1") (pintype "passive"))
    )
    (net (code "2") (name "Net-(C30-Pad1)") (class "Default")
      (node (ref "C30") (pin "1") (pinfunction "1_1") (pintype "passive"))
      (node (ref "C31") (pin "1") (pinfunction "1_1") (pintype "passive"))
      (node (ref "C37") (pin "1") (pinfunction "1_1") (pintype "passive"))
      (node (ref "C38") (pin "1") (pinfunction "1_1") (pintype "passive"))
      (node (ref "C39") (pin "1") (pinfunction "1_1") (pintype "passive"))
      (node (ref "C40") (pin "1") (pinfunction "1_1") (pintype "passive"))
      (node (ref "C41") (pin "1") (pinfunction "1_1") (pintype "passive"))
      (node (ref "C42") (pin "1") (pinfunction "1_1") (pintype "passive"))
      (node (ref "IC1") (pin "AA29") (pinfunction "DIGPRVDD1_AA29") (pintype "power_in"))
      (node (ref "IC1") (pin "AE29") (pinfunction "DIGPRVDD1_AE29") (pintype "power_in"))
      (node (ref "IC1") (pin "L33") (pinfunction "DIGPRVDD1_L33") (pintype "power_in"))
      (node (ref "IC1") (pin "R31") (pinfunction "DIGPRVDD1_R31") (pintype "power_in"))
      (node (ref "R26") (pin "2") (pinfunction "2_2") (pintype "passive"))
      (node (ref "R27") (pin "2") (pinfunction "2_2") (pintype "passive"))
    )
    (net (code "3") (name "Net-(C59-Pad2)") (class "Default")
      (node (ref "C59") (pin "2") (pinfunction "2_2") (pintype "passive"))
      (node (ref "FR12") (pin "1") (pinfunction "1_1") (pintype "passive"))
      (node (ref "R28") (pin "2") (pinfunction "2_2") (pintype "passive"))
      (node (ref "R29") (pin "2") (pinfunction "2_2") (pintype "passive"))
    )
    (net (code "4") (name "Net-(C74-Pad1)") (class "Default")
      (node (ref "C74") (pin "1") (pinfunction "1_1") (pintype "passive"))
      (node (ref "C75") (pin "1") (pinfunction "1_1") (pintype "passive"))
      (node (ref "IC1") (pin "H32") (pinfunction "DIGPRVDD2_H32") (pintype "power_in"))
      (node (ref "R36") (pin "2") (pinfunction "2_2") (pintype "passive"))
    )
    (net (code "5") (name "Net-(C76-Pad1)") (class "Default")
      (node (ref "C76") (pin "1") (pinfunction "1_1") (pintype "passive"))
      (node (ref "C77") (pin "1") (pinfunction "1_1") (pintype "passive"))
      (node (ref "IC1") (pin "T32") (pinfunction "DIGPRVDD2_T32") (pintype "power_in"))
      (node (ref "R35") (pin "2") (pinfunction "2_2") (pintype "passive"))
    )
    (net (code "6") (name "Net-(C78-Pad1)") (class "Default")
      (node (ref "C78") (pin "1") (pinfunction "1_1") (pintype "passive"))
      (node (ref "C79") (pin "1") (pinfunction "1_1") (pintype "passive"))
      (node (ref "IC1") (pin "W33") (pinfunction "DIGPRVDD2_W33") (pintype "power_in"))
      (node (ref "R34") (pin "2") (pinfunction "2_2") (pintype "passive"))
    )
    (net (code "7") (name "Net-(C80-Pad1)") (class "Default")
      (node (ref "C80") (pin "1") (pinfunction "1_1") (pintype "passive"))
      (node (ref "C81") (pin "1") (pinfunction "1_1") (pintype "passive"))
      (node (ref "IC1") (pin "AH30") (pinfunction "DIGPRVDD2_AH30") (pintype "power_in"))
      (node (ref "R32") (pin "2") (pinfunction "2_2") (pintype "passive"))
    )
    (net (code "8") (name "Net-(C95-Pad1)") (class "Default")
      (node (ref "C95") (pin "1") (pinfunction "1_1") (pintype "passive"))
      (node (ref "FR34") (pin "2") (pinfunction "2_2") (pintype "passive"))
      (node (ref "R41") (pin "2") (pinfunction "2_2") (pintype "passive"))
    )
    (net (code "9") (name "Net-(C96-Pad1)") (class "Default")
      (node (ref "C96") (pin "1") (pinfunction "1_1") (pintype "passive"))
      (node (ref "FR33") (pin "1") (pinfunction "1_1") (pintype "passive"))
      (node (ref "R40") (pin "1") (pinfunction "1_1") (pintype "passive"))
    )
    (net (code "10") (name "Net-(IC1E-DIGPRPOC)") (class "Default")
      (node (ref "C72") (pin "1") (pinfunction "1_1") (pintype "passive"))
      (node (ref "C73") (pin "1") (pinfunction "1_1") (pintype "passive"))
      (node (ref "IC1") (pin "W31") (pinfunction "DIGPRPOC_W31") (pintype "power_in"))
      (node (ref "R37") (pin "2") (pinfunction "2_2") (pintype "passive"))
    )
    (net (code "11") (name "Net-(IC1E-VDD18_BIAS)") (class "Default")
      (node (ref "C88") (pin "1") (pinfunction "1_1") (pintype "passive"))
      (node (ref "FR30") (pin "1") (pinfunction "1_1") (pintype "passive"))
      (node (ref "IC1") (pin "E17") (pinfunction "VDD18_BIAS_E17") (pintype "power_in"))
    )
    (net (code "12") (name "Net-(IC1E-VDD18_DIG)") (class "Default")
      (node (ref "C67") (pin "1") (pinfunction "1_1") (pintype "passive"))
      (node (ref "IC1") (pin "D24") (pinfunction "VDD18_DIG_D24") (pintype "power_in"))
      (node (ref "R30") (pin "1") (pinfunction "1_1") (pintype "passive"))
    )
    (net (code "13") (name "Net-(IC1E-VDD18_LDO_RX)") (class "Default")
      (node (ref "C91") (pin "1") (pinfunction "1_1") (pintype "passive"))
      (node (ref "FR27") (pin "2") (pinfunction "2_2") (pintype "passive"))
      (node (ref "IC1") (pin "AE3") (pinfunction "VDD18_TIA_RFE_AE3") (pintype "power_in"))
      (node (ref "IC1") (pin "AF4") (pinfunction "VDD18_LDO_RX_AF4") (pintype "power_in"))
    )
    (net (code "14") (name "Net-(IC1E-VDD18_LDO_TX)") (class "Default")
      (node (ref "C92") (pin "1") (pinfunction "1_1") (pintype "passive"))
      (node (ref "FR26") (pin "2") (pinfunction "2_2") (pintype "passive"))
      (node (ref "IC1") (pin "N1") (pinfunction "VDD18_LDO_TX_N1") (pintype "power_in"))
    )
    (net (code "15") (name "Net-(IC1E-VDD18_RXBUF)") (class "Default")
      (node (ref "C93") (pin "1") (pinfunction "1_1") (pintype "passive"))
      (node (ref "FR34") (pin "1") (pinfunction "1_1") (pintype "passive"))
      (node (ref "IC1") (pin "AM26") (pinfunction "VDD18_RXBUF_AM26") (pintype "power_in"))
    )
    (net (code "16") (name "Net-(IC1E-VDD18_SXR)") (class "Default")
      (node (ref "C90") (pin "1") (pinfunction "1_1") (pintype "passive"))
      (node (ref "FR28") (pin "1") (pinfunction "1_1") (pintype "passive"))
      (node (ref "IC1") (pin "AM18") (pinfunction "VDD18_SXR_AM18") (pintype "power_in"))
    )
    (net (code "17") (name "Net-(IC1E-VDD18_TRF)") (class "Default")
      (node (ref "C87") (pin "1") (pinfunction "1_1") (pintype "passive"))
      (node (ref "FR31") (pin "1") (pinfunction "1_1") (pintype "passive"))
      (node (ref "IC1") (pin "D16") (pinfunction "VDD18_TRF_D16") (pintype "power_in"))
    )
    (net (code "18") (name "Net-(IC1E-VDD18_TXBUF)") (class "Default")
      (node (ref "C94") (pin "1") (pinfunction "1_1") (pintype "passive"))
      (node (ref "FR33") (pin "2") (pinfunction "2_2") (pintype "passive"))
      (node (ref "IC1") (pin "H6") (pinfunction "VDD18_TXBUF_H6") (pintype "power_in"))
    )
    (net (code "19") (name "Net-(IC1E-VDD18_VCO_CGEN)") (class "Default")
      (node (ref "C86") (pin "1") (pinfunction "1_1") (pintype "passive"))
      (node (ref "FR32") (pin "1") (pinfunction "1_1") (pintype "passive"))
      (node (ref "IC1") (pin "E21") (pinfunction "VDD18_VCO_CGEN_E21") (pintype "power_in"))
    )
    (net (code "20") (name "Net-(IC1E-VDD18_VCO_SXR)") (class "Default")
      (node (ref "C89") (pin "1") (pinfunction "1_1") (pintype "passive"))
      (node (ref "FR29") (pin "1") (pinfunction "1_1") (pintype "passive"))
      (node (ref "IC1") (pin "AK22") (pinfunction "VDD18_VCO_SXR_AK22") (pintype "power_in"))
    )
    (net (code "21") (name "Net-(IC1E-VDD18_VCO_SXT)") (class "Default")
      (node (ref "C85") (pin "1") (pinfunction "1_1") (pintype "passive"))
      (node (ref "FR24") (pin "1") (pinfunction "1_1") (pintype "passive"))
      (node (ref "IC1") (pin "G3") (pinfunction "VDD18_VCO_SXT_G3") (pintype "power_in"))
    )
    (net (code "22") (name "Net-(IC1F-DVDD_CGEN)") (class "Default")
      (node (ref "C32") (pin "1") (pinfunction "1_1") (pintype "passive"))
      (node (ref "C33") (pin "1") (pinfunction "1_1") (pintype "passive"))
      (node (ref "C34") (pin "1") (pinfunction "1_1") (pintype "passive"))
      (node (ref "FR3") (pin "1") (pinfunction "1_1") (pintype "passive"))
      (node (ref "IC1") (pin "A17") (pinfunction "DVDD_CGEN_A17") (pintype "power_in"))
      (node (ref "IC1") (pin "C25") (pinfunction "VDD12_DIG_C25") (pintype "power_in"))
      (node (ref "IC1") (pin "F24") (pinfunction "VDD_SPI_BUF_F24") (pintype "power_in"))
    )
    (net (code "23") (name "Net-(IC1F-DVDD_SXR)") (class "Default")
      (node (ref "C36") (pin "1") (pinfunction "1_1") (pintype "passive"))
      (node (ref "FR1") (pin "1") (pinfunction "1_1") (pintype "passive"))
      (node (ref "IC1") (pin "AL21") (pinfunction "DVDD_SXR_AL21") (pintype "power_in"))
    )
    (net (code "24") (name "Net-(IC1F-DVDD_SXT)") (class "Default")
      (node (ref "C35") (pin "2") (pinfunction "2_2") (pintype "passive"))
      (node (ref "FR2") (pin "1") (pinfunction "1_1") (pintype "passive"))
      (node (ref "IC1") (pin "M4") (pinfunction "DVDD_SXT_M4") (pintype "power_in"))
    )
    (net (code "25") (name "Net-(IC1F-VDD12O_VCO_SXT)") (class "Default")
      (node (ref "C58") (pin "2") (pinfunction "2_2") (pintype "passive"))
      (node (ref "FR4") (pin "1") (pinfunction "1_1") (pintype "passive"))
      (node (ref "IC1") (pin "J5") (pinfunction "VDD12O_VCO_SXT_J5") (pintype "power_in"))
      (node (ref "IC1") (pin "K6") (pinfunction "VDD12_VCO_SXT_K6") (pintype "power_in"))
    )
    (net (code "26") (name "Net-(IC1F-VDD12_LNA_RFE)") (class "Default")
      (node (ref "C55") (pin "1") (pinfunction "1_1") (pintype "passive"))
      (node (ref "FR8") (pin "1") (pinfunction "1_1") (pintype "passive"))
      (node (ref "IC1") (pin "AG5") (pinfunction "VDD12_LNA_RFE_AG5") (pintype "power_in"))
    )
    (net (code "27") (name "Net-(IC1F-VDD12_RXBUF)") (class "Default")
      (node (ref "C51") (pin "1") (pinfunction "1_1") (pintype "passive"))
      (node (ref "IC1") (pin "AP26") (pinfunction "VDD12_RXBUF_AP26") (pintype "power_in"))
      (node (ref "R29") (pin "1") (pinfunction "1_1") (pintype "passive"))
    )
    (net (code "28") (name "Net-(IC1F-VDD12_TIA_RFE)") (class "Default")
      (node (ref "C56") (pin "2") (pinfunction "2_2") (pintype "passive"))
      (node (ref "FR7") (pin "1") (pinfunction "1_1") (pintype "passive"))
      (node (ref "IC1") (pin "AD6") (pinfunction "VDD12_TIA_RFE_AD6") (pintype "power_in"))
    )
    (net (code "29") (name "Net-(IC1F-VDD12_TXBUF)") (class "Default")
      (node (ref "C43") (pin "1") (pinfunction "1_1") (pintype "passive"))
      (node (ref "IC1") (pin "G5") (pinfunction "VDD12_TXBUF_G5") (pintype "power_in"))
      (node (ref "R28") (pin "1") (pinfunction "1_1") (pintype "passive"))
    )
    (net (code "30") (name "Net-(IC1F-VDD12_VCO_SXR)") (class "Default")
      (node (ref "C52") (pin "1") (pinfunction "1_1") (pintype "passive"))
      (node (ref "FR11") (pin "1") (pinfunction "1_1") (pintype "passive"))
      (node (ref "IC1") (pin "AN23") (pinfunction "VDD12_VCO_SXR_AN23") (pintype "power_in"))
    )
    (net (code "31") (name "Net-(IC1F-VDD14_LNA_RFE)") (class "Default")
      (node (ref "C63") (pin "1") (pinfunction "1_1") (pintype "passive"))
      (node (ref "C64") (pin "1") (pinfunction "1_1") (pintype "passive"))
      (node (ref "C65") (pin "1") (pinfunction "1_1") (pintype "passive"))
      (node (ref "FR20") (pin "1") (pinfunction "1_1") (pintype "passive"))
      (node (ref "IC1") (pin "AD4") (pinfunction "VDD14_RBB_AD4") (pintype "power_in"))
      (node (ref "IC1") (pin "AF2") (pinfunction "VDD14_TIA_RFE_AF2") (pintype "power_in"))
      (node (ref "IC1") (pin "AF6") (pinfunction "VDD14_LNA_RFE_AF6") (pintype "power_in"))
    )
    (net (code "32") (name "Net-(IC1F-VDD14_VCO_CGEN)") (class "Default")
      (node (ref "C61") (pin "1") (pinfunction "1_1") (pintype "passive"))
      (node (ref "C62") (pin "1") (pinfunction "1_1") (pintype "passive"))
      (node (ref "FR21") (pin "1") (pinfunction "1_1") (pintype "passive"))
      (node (ref "IC1") (pin "C21") (pinfunction "VDD14_VCO_CGEN_C21") (pintype "power_in"))
    )
    (net (code "33") (name "Net-(IC1F-VDDO_DIV_SXT)") (class "Default")
      (node (ref "C60") (pin "1") (pinfunction "1_1") (pintype "passive"))
      (node (ref "FR18") (pin "1") (pinfunction "1_1") (pintype "passive"))
      (node (ref "IC1") (pin "K2") (pinfunction "VDDO_DIV_SXT_K2") (pintype "power_in"))
      (node (ref "IC1") (pin "L5") (pinfunction "VDD_DIV_SXT_L5") (pintype "power_in"))
    )
    (net (code "34") (name "Net-(IC1F-VDDO_TLOBUF_TRF)") (class "Default")
      (node (ref "C45") (pin "1") (pinfunction "1_1") (pintype "passive"))
      (node (ref "FR17") (pin "1") (pinfunction "1_1") (pintype "passive"))
      (node (ref "IC1") (pin "D6") (pinfunction "VDDO_TLOBUF_TRF_D6") (pintype "power_in"))
      (node (ref "IC1") (pin "F8") (pinfunction "VDD_TLOBUF_TRF_F8") (pintype "power_in"))
    )
    (net (code "35") (name "Net-(IC1F-VDD_AFE)") (class "Default")
      (node (ref "C50") (pin "1") (pinfunction "1_1") (pintype "passive"))
      (node (ref "FR13") (pin "1") (pinfunction "1_1") (pintype "passive"))
      (node (ref "IC1") (pin "AJ25") (pinfunction "VDD_AFE_AJ25") (pintype "power_in"))
    )
    (net (code "36") (name "Net-(IC1F-VDD_CP_CGEN)") (class "Default")
      (node (ref "C49") (pin "2") (pinfunction "2_2") (pintype "passive"))
      (node (ref "FR14") (pin "1") (pinfunction "1_1") (pintype "passive"))
      (node (ref "IC1") (pin "F20") (pinfunction "VDD_CP_CGEN_F20") (pintype "power_in"))
    )
    (net (code "37") (name "Net-(IC1F-VDD_CP_SXR)") (class "Default")
      (node (ref "C54") (pin "1") (pinfunction "1_1") (pintype "passive"))
      (node (ref "FR9") (pin "1") (pinfunction "1_1") (pintype "passive"))
      (node (ref "IC1") (pin "AL19") (pinfunction "VDD_CP_SXR_AL19") (pintype "power_in"))
    )
    (net (code "38") (name "Net-(IC1F-VDD_CP_SXT)") (class "Default")
      (node (ref "C57") (pin "1") (pinfunction "1_1") (pintype "passive"))
      (node (ref "FR5") (pin "1") (pinfunction "1_1") (pintype "passive"))
      (node (ref "IC1") (pin "J3") (pinfunction "VDD_CP_SXT_J3") (pintype "power_in"))
    )
    (net (code "39") (name "Net-(IC1F-VDD_DIV_CGEN)") (class "Default")
      (node (ref "C47") (pin "1") (pinfunction "1_1") (pintype "passive"))
      (node (ref "C48") (pin "1") (pinfunction "1_1") (pintype "passive"))
      (node (ref "FR15") (pin "1") (pinfunction "1_1") (pintype "passive"))
      (node (ref "IC1") (pin "E19") (pinfunction "VDD_DIV_CGEN_E19") (pintype "power_in"))
    )
    (net (code "40") (name "Net-(IC1F-VDD_DIV_SXR)") (class "Default")
      (node (ref "C53") (pin "1") (pinfunction "1_1") (pintype "passive"))
      (node (ref "FR10") (pin "1") (pinfunction "1_1") (pintype "passive"))
      (node (ref "IC1") (pin "AM20") (pinfunction "VDD_DIV_SXR_AM20") (pintype "power_in"))
    )
    (net (code "41") (name "Net-(IC1F-VDD_MXLOBUF_RFE)") (class "Default")
      (node (ref "C66") (pin "1") (pinfunction "1_1") (pintype "passive"))
      (node (ref "FR19") (pin "1") (pinfunction "1_1") (pintype "passive"))
      (node (ref "IC1") (pin "AN17") (pinfunction "VDD_MXLOBUF_RFE_AN17") (pintype "power_in"))
    )
    (net (code "42") (name "Net-(IC1F-VDD_TBB)") (class "Default")
      (node (ref "C44") (pin "1") (pinfunction "1_1") (pintype "passive"))
      (node (ref "FR6") (pin "1") (pinfunction "1_1") (pintype "passive"))
      (node (ref "IC1") (pin "P4") (pinfunction "VDD_TBB_P4") (pintype "power_in"))
    )
    (net (code "43") (name "Net-(IC1F-VDD_TPAD_TRF)") (class "Default")
      (node (ref "C46") (pin "1") (pinfunction "1_1") (pintype "passive"))
      (node (ref "FR16") (pin "1") (pinfunction "1_1") (pintype "passive"))
      (node (ref "IC1") (pin "B16") (pinfunction "VDD_TPAD_TRF_B16") (pintype "power_in"))
    )
    (net (code "44") (name "Net-(IC5-ADJ)") (class "Default")
      (node (ref "IC5") (pin "5") (pinfunction "ADJ_5") (pintype "input"))
      (node (ref "R31") (pin "1") (pinfunction "1_1") (pintype "passive"))
      (node (ref "R33") (pin "2") (pinfunction "2_2") (pintype "passive"))
    )
    (net (code "45") (name "Net-(IC5-EN)") (class "Default")
      (node (ref "C68") (pin "2") (pinfunction "2_2") (pintype "passive"))
      (node (ref "FR22") (pin "2") (pinfunction "2_2") (pintype "passive"))
      (node (ref "IC5") (pin "1") (pinfunction "EN_1") (pintype "input"))
      (node (ref "IC5") (pin "6") (pinfunction "Vin_6") (pintype "input"))
    )
    (net (code "46") (name "Net-(IC5-PG)") (class "Default")
      (node (ref "C71") (pin "2") (pinfunction "2_2") (pintype "passive"))
      (node (ref "IC5") (pin "3") (pinfunction "PG_3") (pintype "output"))
    )
    (net (code "47") (name "Net-(IC6-ADJ)") (class "Default")
      (node (ref "IC6") (pin "5") (pinfunction "ADJ_5") (pintype "input"))
      (node (ref "R38") (pin "1") (pinfunction "1_1") (pintype "passive"))
      (node (ref "R39") (pin "2") (pinfunction "2_2") (pintype "passive"))
    )
    (net (code "48") (name "Net-(IC6-EN)") (class "Default")
      (node (ref "C82") (pin "2") (pinfunction "2_2") (pintype "passive"))
      (node (ref "FR25") (pin "2") (pinfunction "2_2") (pintype "passive"))
      (node (ref "IC6") (pin "1") (pinfunction "EN_1") (pintype "input"))
      (node (ref "IC6") (pin "6") (pinfunction "Vin_6") (pintype "input"))
    )
    (net (code "49") (name "Net-(IC6-PG)") (class "Default")
      (node (ref "C84") (pin "2") (pinfunction "2_2") (pintype "passive"))
      (node (ref "IC6") (pin "3") (pinfunction "PG_3") (pintype "output"))
    )
    (net (code "50") (name "VCC1P4_LMS") (class "Default")
      (node (ref "C83") (pin "2") (pinfunction "2_2") (pintype "passive"))
      (node (ref "FR18") (pin "2") (pinfunction "2_2") (pintype "passive"))
      (node (ref "FR19") (pin "2") (pinfunction "2_2") (pintype "passive"))
      (node (ref "FR20") (pin "2") (pinfunction "2_2") (pintype "passive"))
      (node (ref "FR21") (pin "2") (pinfunction "2_2") (pintype "passive"))
      (node (ref "IC6") (pin "4") (pinfunction "Vout_4") (pintype "output"))
      (node (ref "R26") (pin "1") (pinfunction "1_1") (pintype "passive"))
      (node (ref "R38") (pin "2") (pinfunction "2_2") (pintype "passive"))
    )
    (net (code "51") (name "VCC1P8") (class "Default")
      (node (ref "FR23") (pin "1") (pinfunction "1_1") (pintype "passive"))
    )
    (net (code "52") (name "VCC1P8_LMS") (class "Default")
      (node (ref "C70") (pin "2") (pinfunction "2_2") (pintype "passive"))
      (node (ref "FR22") (pin "1") (pinfunction "1_1") (pintype "passive"))
      (node (ref "FR23") (pin "2") (pinfunction "2_2") (pintype "passive"))
      (node (ref "FR24") (pin "2") (pinfunction "2_2") (pintype "passive"))
      (node (ref "FR25") (pin "1") (pinfunction "1_1") (pintype "passive"))
      (node (ref "FR26") (pin "1") (pinfunction "1_1") (pintype "passive"))
      (node (ref "FR27") (pin "1") (pinfunction "1_1") (pintype "passive"))
      (node (ref "FR28") (pin "2") (pinfunction "2_2") (pintype "passive"))
      (node (ref "FR29") (pin "2") (pinfunction "2_2") (pintype "passive"))
      (node (ref "FR30") (pin "2") (pinfunction "2_2") (pintype "passive"))
      (node (ref "FR31") (pin "2") (pinfunction "2_2") (pintype "passive"))
      (node (ref "FR32") (pin "2") (pinfunction "2_2") (pintype "passive"))
      (node (ref "R30") (pin "2") (pinfunction "2_2") (pintype "passive"))
      (node (ref "R40") (pin "2") (pinfunction "2_2") (pintype "passive"))
      (node (ref "R41") (pin "1") (pinfunction "1_1") (pintype "passive"))
    )
    (net (code "53") (name "VCC1P25_LMS") (class "Default")
      (node (ref "C69") (pin "2") (pinfunction "2_2") (pintype "passive"))
      (node (ref "FR1") (pin "2") (pinfunction "2_2") (pintype "passive"))
      (node (ref "FR10") (pin "2") (pinfunction "2_2") (pintype "passive"))
      (node (ref "FR11") (pin "2") (pinfunction "2_2") (pintype "passive"))
      (node (ref "FR12") (pin "2") (pinfunction "2_2") (pintype "passive"))
      (node (ref "FR13") (pin "2") (pinfunction "2_2") (pintype "passive"))
      (node (ref "FR14") (pin "2") (pinfunction "2_2") (pintype "passive"))
      (node (ref "FR15") (pin "2") (pinfunction "2_2") (pintype "passive"))
      (node (ref "FR16") (pin "2") (pinfunction "2_2") (pintype "passive"))
      (node (ref "FR17") (pin "2") (pinfunction "2_2") (pintype "passive"))
      (node (ref "FR2") (pin "2") (pinfunction "2_2") (pintype "passive"))
      (node (ref "FR3") (pin "2") (pinfunction "2_2") (pintype "passive"))
      (node (ref "FR4") (pin "2") (pinfunction "2_2") (pintype "passive"))
      (node (ref "FR5") (pin "2") (pinfunction "2_2") (pintype "passive"))
      (node (ref "FR6") (pin "2") (pinfunction "2_2") (pintype "passive"))
      (node (ref "FR7") (pin "2") (pinfunction "2_2") (pintype "passive"))
      (node (ref "FR8") (pin "2") (pinfunction "2_2") (pintype "passive"))
      (node (ref "FR9") (pin "2") (pinfunction "2_2") (pintype "passive"))
      (node (ref "IC5") (pin "4") (pinfunction "Vout_4") (pintype "output"))
      (node (ref "R27") (pin "1") (pinfunction "1_1") (pintype "passive"))
      (node (ref "R31") (pin "2") (pinfunction "2_2") (pintype "passive"))
    )
    (net (code "54") (name "VDIO_LMS") (class "Default")
      (node (ref "R32") (pin "1") (pinfunction "1_1") (pintype "passive"))
      (node (ref "R34") (pin "1") (pinfunction "1_1") (pintype "passive"))
      (node (ref "R35") (pin "1") (pinfunction "1_1") (pintype "passive"))
      (node (ref "R36") (pin "1") (pinfunction "1_1") (pintype "passive"))
      (node (ref "R37") (pin "1") (pinfunction "1_1") (pintype "passive"))
    )
  )
)
